# STM32F407_Core.net
KiCad netlist of a schematic drawn in Altium Designer
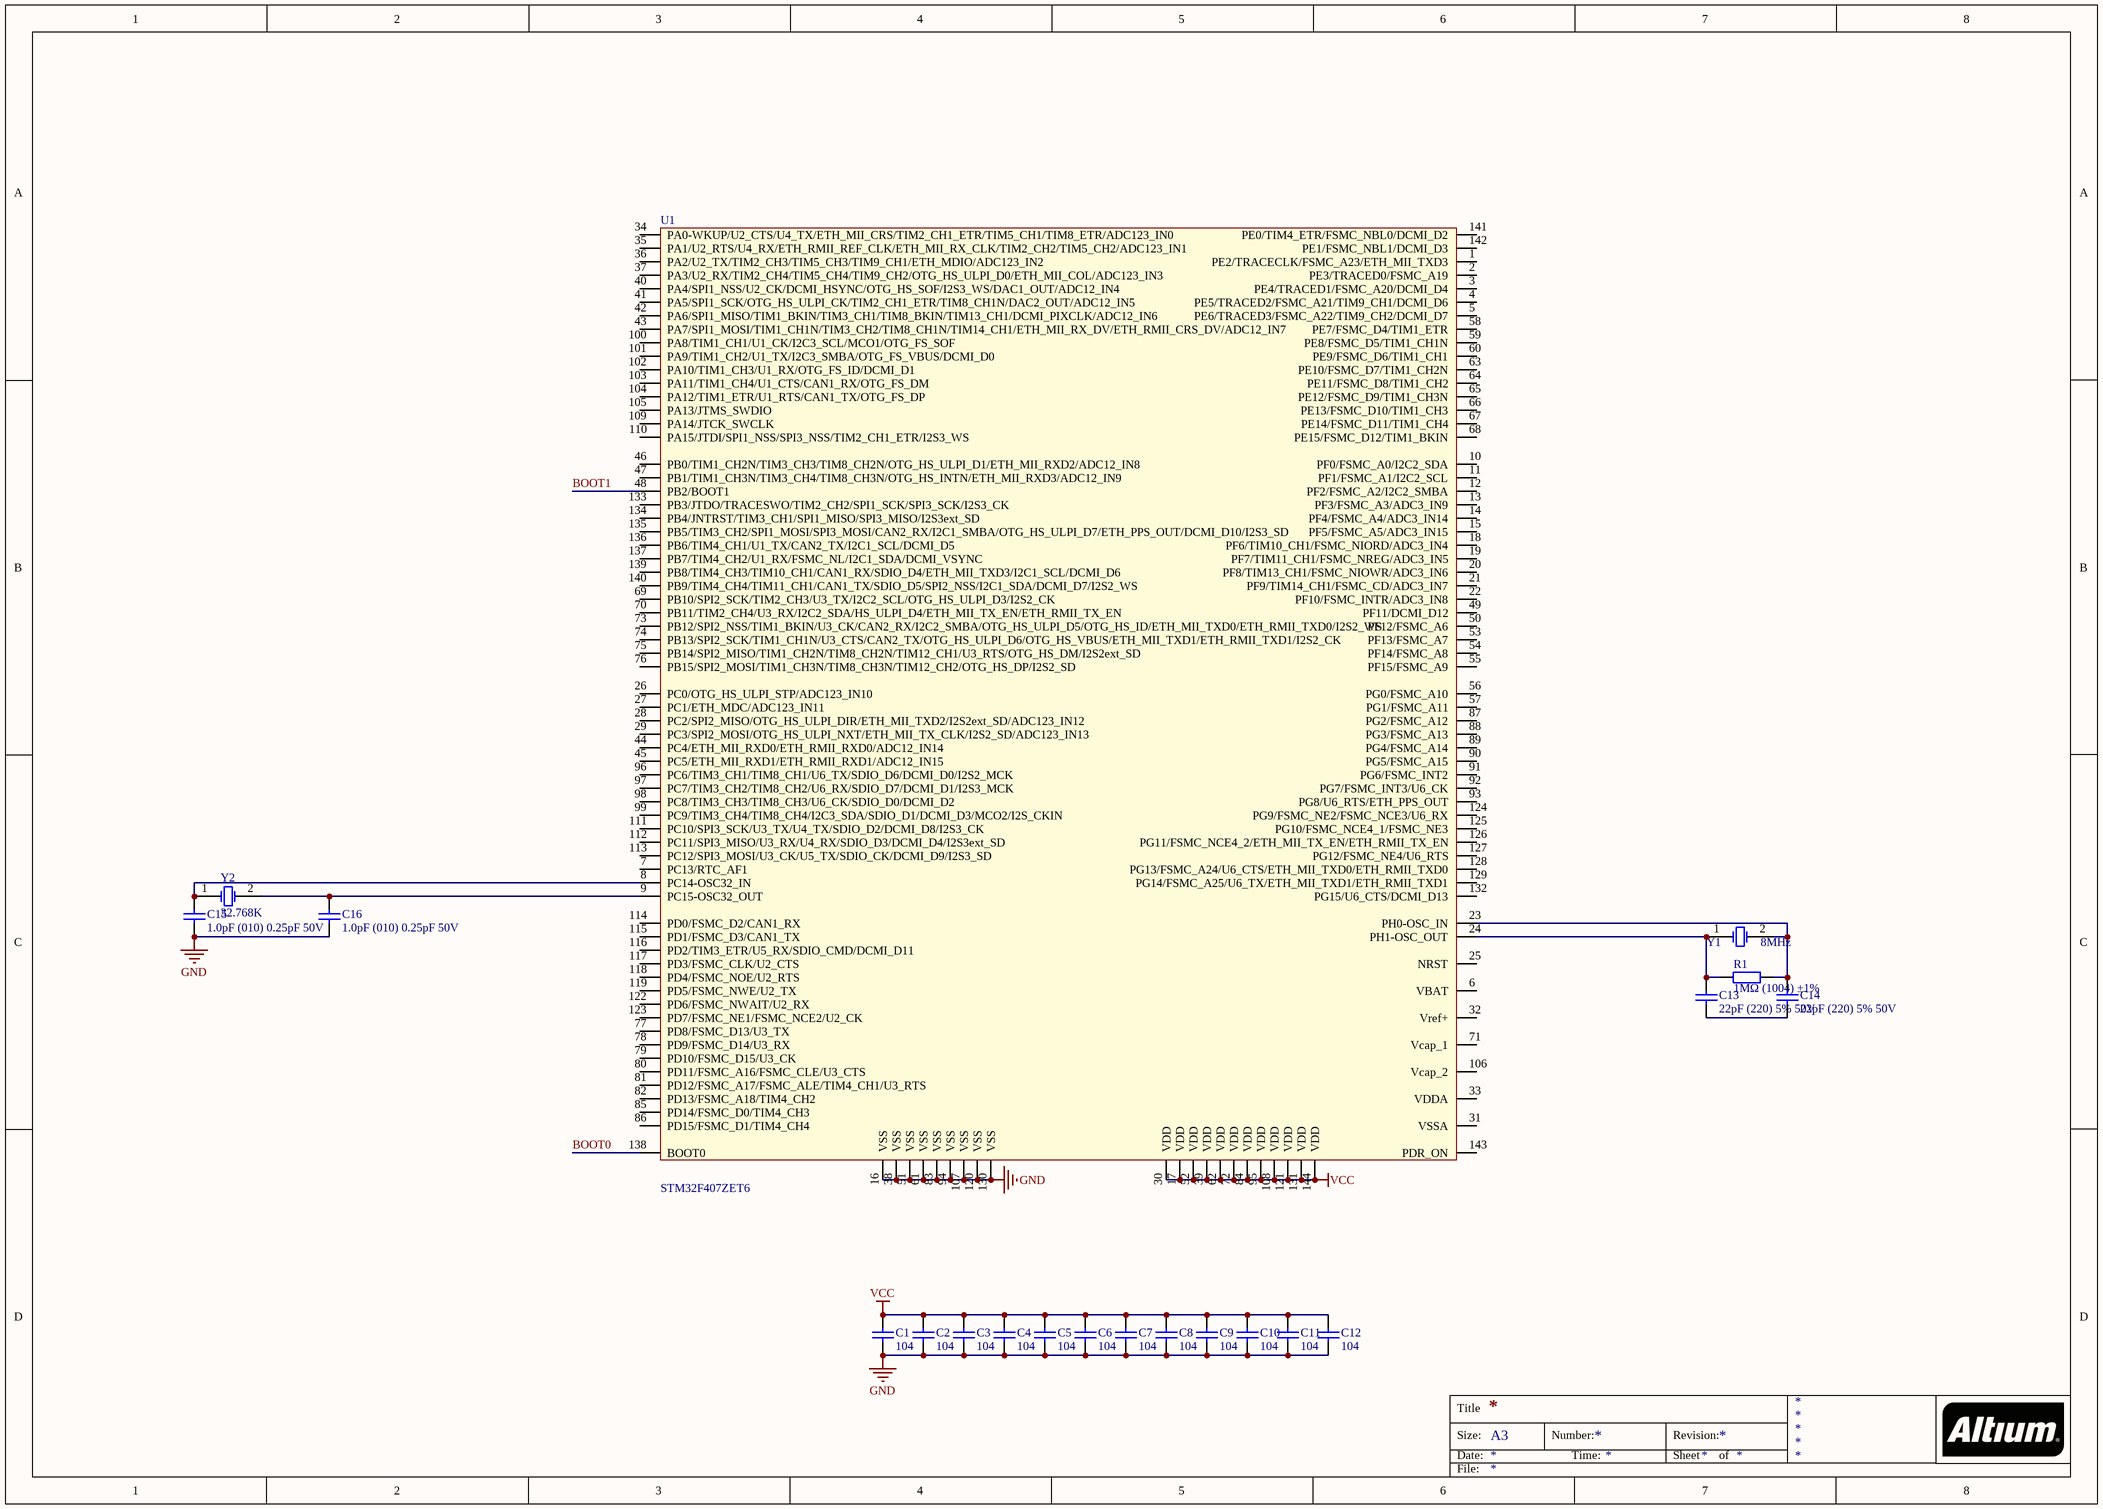
[diagram p0: STM32F407_Core.SchDoc]

(export (version "E")
  (design (tool "Eeschema 10.0.6"))
  (components
    (comp (ref "C1")
      (value "104")
      (footprint "LC-0805_C")
      (description "贴片电容")
      (libsource (lib "Miscellaneous Devices LC") (part "0805 100nF(104) 10% 50V"))
    )
    (comp (ref "C2")
      (value "104")
      (footprint "LC-0805_C")
      (description "贴片电容")
      (libsource (lib "Miscellaneous Devices LC") (part "0805 100nF(104) 10% 50V"))
    )
    (comp (ref "C3")
      (value "104")
      (footprint "LC-0805_C")
      (description "贴片电容")
      (libsource (lib "Miscellaneous Devices LC") (part "0805 100nF(104) 10% 50V"))
    )
    (comp (ref "C4")
      (value "104")
      (footprint "LC-0805_C")
      (description "贴片电容")
      (libsource (lib "Miscellaneous Devices LC") (part "0805 100nF(104) 10% 50V"))
    )
    (comp (ref "C5")
      (value "104")
      (footprint "LC-0805_C")
      (description "贴片电容")
      (libsource (lib "Miscellaneous Devices LC") (part "0805 100nF(104) 10% 50V"))
    )
    (comp (ref "C6")
      (value "104")
      (footprint "LC-0805_C")
      (description "贴片电容")
      (libsource (lib "Miscellaneous Devices LC") (part "0805 100nF(104) 10% 50V"))
    )
    (comp (ref "C7")
      (value "104")
      (footprint "LC-0805_C")
      (description "贴片电容")
      (libsource (lib "Miscellaneous Devices LC") (part "0805 100nF(104) 10% 50V"))
    )
    (comp (ref "C8")
      (value "104")
      (footprint "LC-0805_C")
      (description "贴片电容")
      (libsource (lib "Miscellaneous Devices LC") (part "0805 100nF(104) 10% 50V"))
    )
    (comp (ref "C9")
      (value "104")
      (footprint "LC-0805_C")
      (description "贴片电容")
      (libsource (lib "Miscellaneous Devices LC") (part "0805 100nF(104) 10% 50V"))
    )
    (comp (ref "C10")
      (value "104")
      (footprint "LC-0805_C")
      (description "贴片电容")
      (libsource (lib "Miscellaneous Devices LC") (part "0805 100nF(104) 10% 50V"))
    )
    (comp (ref "C11")
      (value "104")
      (footprint "LC-0805_C")
      (description "贴片电容")
      (libsource (lib "Miscellaneous Devices LC") (part "0805 100nF(104) 10% 50V"))
    )
    (comp (ref "C12")
      (value "104")
      (footprint "LC-0805_C")
      (description "贴片电容")
      (libsource (lib "Miscellaneous Devices LC") (part "0805 100nF(104) 10% 50V"))
    )
    (comp (ref "C13")
      (value "22pF (220) 5% 50V")
      (footprint "LC-0805_C")
      (description "贴片电容")
      (libsource (lib "Miscellaneous Devices LC") (part "0805 22pF (220) 5% 50V"))
    )
    (comp (ref "C14")
      (value "22pF (220) 5% 50V")
      (footprint "LC-0805_C")
      (description "贴片电容")
      (libsource (lib "Miscellaneous Devices LC") (part "0805 22pF (220) 5% 50V"))
    )
    (comp (ref "C15")
      (value "1.0pF (010) 0.25pF 50V")
      (footprint "LC-0805_C")
      (description "贴片电容")
      (libsource (lib "Miscellaneous Devices LC") (part "0805 1.0pF (010) 0.25pF 50V"))
    )
    (comp (ref "C16")
      (value "1.0pF (010) 0.25pF 50V")
      (footprint "LC-0805_C")
      (description "贴片电容")
      (libsource (lib "Miscellaneous Devices LC") (part "0805 1.0pF (010) 0.25pF 50V"))
    )
    (comp (ref "R1")
      (value "1MΩ (1004) ±1%")
      (footprint "LC-0805_R")
      (description "贴片电阻")
      (libsource (lib "Miscellaneous Devices LC") (part "0805 1MΩ (1004) 1%"))
    )
    (comp (ref "U1")
      (value "STM32F407ZET6")
      (footprint "LQFP144")
      (libsource (lib "Explorer STM32F407封装库") (part "STM32F407ZET6"))
    )
    (comp (ref "Y1")
      (value "8MHz")
      (footprint "XTAL_US")
      (description "Crystal Oscillator")
      (fields (field (name "PUBLISHER") "Altium Limited"))
      (libsource (lib "Explorer STM32F407封装库") (part "XTAL"))
    )
    (comp (ref "Y2")
      (value "32.768K")
      (footprint "R38")
      (description "Crystal Oscillator")
      (fields (field (name "PUBLISHER") "Altium Limited"))
      (libsource (lib "Miscellaneous Devices") (part "XTAL"))
    )
  )
  (nets
    (net (code "1") (name "/BOOT0") (class "Default")
      (node (ref "U1") (pin "138") (pinfunction "BOOT0_138") (pintype "passive"))
    )
    (net (code "2") (name "/BOOT1") (class "Default")
      (node (ref "U1") (pin "48") (pinfunction "PB2/BOOT1_48") (pintype "passive"))
    )
    (net (code "3") (name "GND") (class "Default")
      (node (ref "C1") (pin "1") (pinfunction "1_1") (pintype "passive"))
      (node (ref "C10") (pin "1") (pinfunction "1_1") (pintype "passive"))
      (node (ref "C11") (pin "1") (pinfunction "1_1") (pintype "passive"))
      (node (ref "C12") (pin "1") (pinfunction "1_1") (pintype "passive"))
      (node (ref "C15") (pin "1") (pinfunction "1_1") (pintype "passive"))
      (node (ref "C16") (pin "1") (pinfunction "1_1") (pintype "passive"))
      (node (ref "C2") (pin "1") (pinfunction "1_1") (pintype "passive"))
      (node (ref "C3") (pin "1") (pinfunction "1_1") (pintype "passive"))
      (node (ref "C4") (pin "1") (pinfunction "1_1") (pintype "passive"))
      (node (ref "C5") (pin "1") (pinfunction "1_1") (pintype "passive"))
      (node (ref "C6") (pin "1") (pinfunction "1_1") (pintype "passive"))
      (node (ref "C7") (pin "1") (pinfunction "1_1") (pintype "passive"))
      (node (ref "C8") (pin "1") (pinfunction "1_1") (pintype "passive"))
      (node (ref "C9") (pin "1") (pinfunction "1_1") (pintype "passive"))
      (node (ref "U1") (pin "107") (pinfunction "VSS_107") (pintype "passive"))
      (node (ref "U1") (pin "120") (pinfunction "VSS_120") (pintype "passive"))
      (node (ref "U1") (pin "130") (pinfunction "VSS_130") (pintype "passive"))
      (node (ref "U1") (pin "16") (pinfunction "VSS_16") (pintype "passive"))
      (node (ref "U1") (pin "38") (pinfunction "VSS_38") (pintype "passive"))
      (node (ref "U1") (pin "51") (pinfunction "VSS_51") (pintype "passive"))
      (node (ref "U1") (pin "61") (pinfunction "VSS_61") (pintype "passive"))
      (node (ref "U1") (pin "83") (pinfunction "VSS_83") (pintype "passive"))
      (node (ref "U1") (pin "94") (pinfunction "VSS_94") (pintype "passive"))
    )
    (net (code "4") (name "Net-(C13-Pad1)") (class "Default")
      (node (ref "C13") (pin "1") (pinfunction "1_1") (pintype "passive"))
      (node (ref "C14") (pin "1") (pinfunction "1_1") (pintype "passive"))
    )
    (net (code "5") (name "Net-(U1-PC14-OSC32_IN)") (class "Default")
      (node (ref "C15") (pin "2") (pinfunction "2_2") (pintype "passive"))
      (node (ref "U1") (pin "8") (pinfunction "PC14-OSC32_IN_8") (pintype "passive"))
      (node (ref "Y2") (pin "1") (pinfunction "OSC1_1") (pintype "passive"))
    )
    (net (code "6") (name "Net-(U1-PC15-OSC32_OUT)") (class "Default")
      (node (ref "C16") (pin "2") (pinfunction "2_2") (pintype "passive"))
      (node (ref "U1") (pin "9") (pinfunction "PC15-OSC32_OUT_9") (pintype "passive"))
      (node (ref "Y2") (pin "2") (pinfunction "OSC2_2") (pintype "passive"))
    )
    (net (code "7") (name "Net-(U1-PH0-OSC_IN)") (class "Default")
      (node (ref "C14") (pin "2") (pinfunction "2_2") (pintype "passive"))
      (node (ref "R1") (pin "2") (pinfunction "2_2") (pintype "passive"))
      (node (ref "U1") (pin "23") (pinfunction "PH0-OSC_IN_23") (pintype "passive"))
      (node (ref "Y1") (pin "2") (pinfunction "OSC2_2") (pintype "passive"))
    )
    (net (code "8") (name "Net-(U1-PH1-OSC_OUT)") (class "Default")
      (node (ref "C13") (pin "2") (pinfunction "2_2") (pintype "passive"))
      (node (ref "R1") (pin "1") (pinfunction "1_1") (pintype "passive"))
      (node (ref "U1") (pin "24") (pinfunction "PH1-OSC_OUT_24") (pintype "passive"))
      (node (ref "Y1") (pin "1") (pinfunction "OSC1_1") (pintype "passive"))
    )
    (net (code "9") (name "VCC") (class "Default")
      (node (ref "C1") (pin "2") (pinfunction "2_2") (pintype "passive"))
      (node (ref "C10") (pin "2") (pinfunction "2_2") (pintype "passive"))
      (node (ref "C11") (pin "2") (pinfunction "2_2") (pintype "passive"))
      (node (ref "C12") (pin "2") (pinfunction "2_2") (pintype "passive"))
      (node (ref "C2") (pin "2") (pinfunction "2_2") (pintype "passive"))
      (node (ref "C3") (pin "2") (pinfunction "2_2") (pintype "passive"))
      (node (ref "C4") (pin "2") (pinfunction "2_2") (pintype "passive"))
      (node (ref "C5") (pin "2") (pinfunction "2_2") (pintype "passive"))
      (node (ref "C6") (pin "2") (pinfunction "2_2") (pintype "passive"))
      (node (ref "C7") (pin "2") (pinfunction "2_2") (pintype "passive"))
      (node (ref "C8") (pin "2") (pinfunction "2_2") (pintype "passive"))
      (node (ref "C9") (pin "2") (pinfunction "2_2") (pintype "passive"))
      (node (ref "U1") (pin "108") (pinfunction "VDD_108") (pintype "passive"))
      (node (ref "U1") (pin "121") (pinfunction "VDD_121") (pintype "passive"))
      (node (ref "U1") (pin "131") (pinfunction "VDD_131") (pintype "passive"))
      (node (ref "U1") (pin "144") (pinfunction "VDD_144") (pintype "passive"))
      (node (ref "U1") (pin "17") (pinfunction "VDD_17") (pintype "passive"))
      (node (ref "U1") (pin "30") (pinfunction "VDD_30") (pintype "passive"))
      (node (ref "U1") (pin "39") (pinfunction "VDD_39") (pintype "passive"))
      (node (ref "U1") (pin "52") (pinfunction "VDD_52") (pintype "passive"))
      (node (ref "U1") (pin "62") (pinfunction "VDD_62") (pintype "passive"))
      (node (ref "U1") (pin "72") (pinfunction "VDD_72") (pintype "passive"))
      (node (ref "U1") (pin "84") (pinfunction "VDD_84") (pintype "passive"))
      (node (ref "U1") (pin "95") (pinfunction "VDD_95") (pintype "passive"))
    )
    (net (code "10") (name "unconnected-(U1-NRST-Pad25)") (class "Default")
      (node (ref "U1") (pin "25") (pinfunction "NRST_25") (pintype "passive"))
    )
    (net (code "11") (name "unconnected-(U1-PA0-WKUP{slash}U2_CTS{slash}U4_TX{slash}ETH_MII_CRS{slash}TIM2_CH1_ETR{slash}TIM5_CH1{slash}TIM8_ETR{slash}ADC123_IN0-Pad34)") (class "Default")
      (node (ref "U1") (pin "34") (pinfunction "PA0-WKUP/U2_CTS/U4_TX/ETH_MII_CRS/TIM2_CH1_ETR/TIM5_CH1/TIM8_ETR/ADC123_IN0_34") (pintype "passive"))
    )
    (net (code "12") (name "unconnected-(U1-PA1{slash}U2_RTS{slash}U4_RX{slash}ETH_RMII_REF_CLK{slash}ETH_MII_RX_CLK{slash}TIM2_CH2{slash}TIM5_CH2{slash}ADC123_IN1-Pad35)") (class "Default")
      (node (ref "U1") (pin "35") (pinfunction "PA1/U2_RTS/U4_RX/ETH_RMII_REF_CLK/ETH_MII_RX_CLK/TIM2_CH2/TIM5_CH2/ADC123_IN1_35") (pintype "passive"))
    )
    (net (code "13") (name "unconnected-(U1-PA2{slash}U2_TX{slash}TIM2_CH3{slash}TIM5_CH3{slash}TIM9_CH1{slash}ETH_MDIO{slash}ADC123_IN2-Pad36)") (class "Default")
      (node (ref "U1") (pin "36") (pinfunction "PA2/U2_TX/TIM2_CH3/TIM5_CH3/TIM9_CH1/ETH_MDIO/ADC123_IN2_36") (pintype "passive"))
    )
    (net (code "14") (name "unconnected-(U1-PA3{slash}U2_RX{slash}TIM2_CH4{slash}TIM5_CH4{slash}TIM9_CH2{slash}OTG_HS_ULPI_D0{slash}ETH_MII_COL{slash}ADC123_IN3-Pad37)") (class "Default")
      (node (ref "U1") (pin "37") (pinfunction "PA3/U2_RX/TIM2_CH4/TIM5_CH4/TIM9_CH2/OTG_HS_ULPI_D0/ETH_MII_COL/ADC123_IN3_37") (pintype "passive"))
    )
    (net (code "15") (name "unconnected-(U1-PA4{slash}SPI1_NSS{slash}U2_CK{slash}DCMI_HSYNC{slash}OTG_HS_SOF{slash}I2S3_WS{slash}DAC1_OUT{slash}ADC12_IN4-Pad40)") (class "Default")
      (node (ref "U1") (pin "40") (pinfunction "PA4/SPI1_NSS/U2_CK/DCMI_HSYNC/OTG_HS_SOF/I2S3_WS/DAC1_OUT/ADC12_IN4_40") (pintype "passive"))
    )
    (net (code "16") (name "unconnected-(U1-PA5{slash}SPI1_SCK{slash}OTG_HS_ULPI_CK{slash}TIM2_CH1_ETR{slash}TIM8_CH1N{slash}DAC2_OUT{slash}ADC12_IN5-Pad41)") (class "Default")
      (node (ref "U1") (pin "41") (pinfunction "PA5/SPI1_SCK/OTG_HS_ULPI_CK/TIM2_CH1_ETR/TIM8_CH1N/DAC2_OUT/ADC12_IN5_41") (pintype "passive"))
    )
    (net (code "17") (name "unconnected-(U1-PA6{slash}SPI1_MISO{slash}TIM1_BKIN{slash}TIM3_CH1{slash}TIM8_BKIN{slash}TIM13_CH1{slash}DCMI_PIXCLK{slash}ADC12_IN6-Pad42)") (class "Default")
      (node (ref "U1") (pin "42") (pinfunction "PA6/SPI1_MISO/TIM1_BKIN/TIM3_CH1/TIM8_BKIN/TIM13_CH1/DCMI_PIXCLK/ADC12_IN6_42") (pintype "passive"))
    )
    (net (code "18") (name "unconnected-(U1-PA7{slash}SPI1_MOSI{slash}TIM1_CH1N{slash}TIM3_CH2{slash}TIM8_CH1N{slash}TIM14_CH1{slash}ETH_MII_RX_DV{slash}ETH_RMII_CRS_DV{slash}ADC12_IN7-Pad43)") (class "Default")
      (node (ref "U1") (pin "43") (pinfunction "PA7/SPI1_MOSI/TIM1_CH1N/TIM3_CH2/TIM8_CH1N/TIM14_CH1/ETH_MII_RX_DV/ETH_RMII_CRS_DV/ADC12_IN7_43") (pintype "passive"))
    )
    (net (code "19") (name "unconnected-(U1-PA8{slash}TIM1_CH1{slash}U1_CK{slash}I2C3_SCL{slash}MCO1{slash}OTG_FS_SOF-Pad100)") (class "Default")
      (node (ref "U1") (pin "100") (pinfunction "PA8/TIM1_CH1/U1_CK/I2C3_SCL/MCO1/OTG_FS_SOF_100") (pintype "passive"))
    )
    (net (code "20") (name "unconnected-(U1-PA9{slash}TIM1_CH2{slash}U1_TX{slash}I2C3_SMBA{slash}OTG_FS_VBUS{slash}DCMI_D0-Pad101)") (class "Default")
      (node (ref "U1") (pin "101") (pinfunction "PA9/TIM1_CH2/U1_TX/I2C3_SMBA/OTG_FS_VBUS/DCMI_D0_101") (pintype "passive"))
    )
    (net (code "21") (name "unconnected-(U1-PA10{slash}TIM1_CH3{slash}U1_RX{slash}OTG_FS_ID{slash}DCMI_D1-Pad102)") (class "Default")
      (node (ref "U1") (pin "102") (pinfunction "PA10/TIM1_CH3/U1_RX/OTG_FS_ID/DCMI_D1_102") (pintype "passive"))
    )
    (net (code "22") (name "unconnected-(U1-PA11{slash}TIM1_CH4{slash}U1_CTS{slash}CAN1_RX{slash}OTG_FS_DM-Pad103)") (class "Default")
      (node (ref "U1") (pin "103") (pinfunction "PA11/TIM1_CH4/U1_CTS/CAN1_RX/OTG_FS_DM_103") (pintype "passive"))
    )
    (net (code "23") (name "unconnected-(U1-PA12{slash}TIM1_ETR{slash}U1_RTS{slash}CAN1_TX{slash}OTG_FS_DP-Pad104)") (class "Default")
      (node (ref "U1") (pin "104") (pinfunction "PA12/TIM1_ETR/U1_RTS/CAN1_TX/OTG_FS_DP_104") (pintype "passive"))
    )
    (net (code "24") (name "unconnected-(U1-PA13{slash}JTMS_SWDIO-Pad105)") (class "Default")
      (node (ref "U1") (pin "105") (pinfunction "PA13/JTMS_SWDIO_105") (pintype "passive"))
    )
    (net (code "25") (name "unconnected-(U1-PA14{slash}JTCK_SWCLK-Pad109)") (class "Default")
      (node (ref "U1") (pin "109") (pinfunction "PA14/JTCK_SWCLK_109") (pintype "passive"))
    )
    (net (code "26") (name "unconnected-(U1-PA15{slash}JTDI{slash}SPI1_NSS{slash}SPI3_NSS{slash}TIM2_CH1_ETR{slash}I2S3_WS-Pad110)") (class "Default")
      (node (ref "U1") (pin "110") (pinfunction "PA15/JTDI/SPI1_NSS/SPI3_NSS/TIM2_CH1_ETR/I2S3_WS_110") (pintype "passive"))
    )
    (net (code "27") (name "unconnected-(U1-PB0{slash}TIM1_CH2N{slash}TIM3_CH3{slash}TIM8_CH2N{slash}OTG_HS_ULPI_D1{slash}ETH_MII_RXD2{slash}ADC12_IN8-Pad46)") (class "Default")
      (node (ref "U1") (pin "46") (pinfunction "PB0/TIM1_CH2N/TIM3_CH3/TIM8_CH2N/OTG_HS_ULPI_D1/ETH_MII_RXD2/ADC12_IN8_46") (pintype "passive"))
    )
    (net (code "28") (name "unconnected-(U1-PB1{slash}TIM1_CH3N{slash}TIM3_CH4{slash}TIM8_CH3N{slash}OTG_HS_INTN{slash}ETH_MII_RXD3{slash}ADC12_IN9-Pad47)") (class "Default")
      (node (ref "U1") (pin "47") (pinfunction "PB1/TIM1_CH3N/TIM3_CH4/TIM8_CH3N/OTG_HS_INTN/ETH_MII_RXD3/ADC12_IN9_47") (pintype "passive"))
    )
    (net (code "29") (name "unconnected-(U1-PB3{slash}JTDO{slash}TRACESWO{slash}TIM2_CH2{slash}SPI1_SCK{slash}SPI3_SCK{slash}I2S3_CK-Pad133)") (class "Default")
      (node (ref "U1") (pin "133") (pinfunction "PB3/JTDO/TRACESWO/TIM2_CH2/SPI1_SCK/SPI3_SCK/I2S3_CK_133") (pintype "passive"))
    )
    (net (code "30") (name "unconnected-(U1-PB4{slash}JNTRST{slash}TIM3_CH1{slash}SPI1_MISO{slash}SPI3_MISO{slash}I2S3ext_SD-Pad134)") (class "Default")
      (node (ref "U1") (pin "134") (pinfunction "PB4/JNTRST/TIM3_CH1/SPI1_MISO/SPI3_MISO/I2S3ext_SD_134") (pintype "passive"))
    )
    (net (code "31") (name "unconnected-(U1-PB5{slash}TIM3_CH2{slash}SPI1_MOSI{slash}SPI3_MOSI{slash}CAN2_RX{slash}I2C1_SMBA{slash}OTG_HS_ULPI_D7{slash}ETH_PPS_OUT{slash}DCMI_D10{slash}I2S3_SD-Pad135)") (class "Default")
      (node (ref "U1") (pin "135") (pinfunction "PB5/TIM3_CH2/SPI1_MOSI/SPI3_MOSI/CAN2_RX/I2C1_SMBA/OTG_HS_ULPI_D7/ETH_PPS_OUT/DCMI_D10/I2S3_SD_135") (pintype "passive"))
    )
    (net (code "32") (name "unconnected-(U1-PB6{slash}TIM4_CH1{slash}U1_TX{slash}CAN2_TX{slash}I2C1_SCL{slash}DCMI_D5-Pad136)") (class "Default")
      (node (ref "U1") (pin "136") (pinfunction "PB6/TIM4_CH1/U1_TX/CAN2_TX/I2C1_SCL/DCMI_D5_136") (pintype "passive"))
    )
    (net (code "33") (name "unconnected-(U1-PB7{slash}TIM4_CH2{slash}U1_RX{slash}FSMC_NL{slash}I2C1_SDA{slash}DCMI_VSYNC-Pad137)") (class "Default")
      (node (ref "U1") (pin "137") (pinfunction "PB7/TIM4_CH2/U1_RX/FSMC_NL/I2C1_SDA/DCMI_VSYNC_137") (pintype "passive"))
    )
    (net (code "34") (name "unconnected-(U1-PB8{slash}TIM4_CH3{slash}TIM10_CH1{slash}CAN1_RX{slash}SDIO_D4{slash}ETH_MII_TXD3{slash}I2C1_SCL{slash}DCMI_D6-Pad139)") (class "Default")
      (node (ref "U1") (pin "139") (pinfunction "PB8/TIM4_CH3/TIM10_CH1/CAN1_RX/SDIO_D4/ETH_MII_TXD3/I2C1_SCL/DCMI_D6_139") (pintype "passive"))
    )
    (net (code "35") (name "unconnected-(U1-PB9{slash}TIM4_CH4{slash}TIM11_CH1{slash}CAN1_TX{slash}SDIO_D5{slash}SPI2_NSS{slash}I2C1_SDA{slash}DCMI_D7{slash}I2S2_WS-Pad140)") (class "Default")
      (node (ref "U1") (pin "140") (pinfunction "PB9/TIM4_CH4/TIM11_CH1/CAN1_TX/SDIO_D5/SPI2_NSS/I2C1_SDA/DCMI_D7/I2S2_WS_140") (pintype "passive"))
    )
    (net (code "36") (name "unconnected-(U1-PB10{slash}SPI2_SCK{slash}TIM2_CH3{slash}U3_TX{slash}I2C2_SCL{slash}OTG_HS_ULPI_D3{slash}I2S2_CK-Pad69)") (class "Default")
      (node (ref "U1") (pin "69") (pinfunction "PB10/SPI2_SCK/TIM2_CH3/U3_TX/I2C2_SCL/OTG_HS_ULPI_D3/I2S2_CK_69") (pintype "passive"))
    )
    (net (code "37") (name "unconnected-(U1-PB11{slash}TIM2_CH4{slash}U3_RX{slash}I2C2_SDA{slash}HS_ULPI_D4{slash}ETH_MII_TX_EN{slash}ETH_RMII_TX_EN-Pad70)") (class "Default")
      (node (ref "U1") (pin "70") (pinfunction "PB11/TIM2_CH4/U3_RX/I2C2_SDA/HS_ULPI_D4/ETH_MII_TX_EN/ETH_RMII_TX_EN_70") (pintype "passive"))
    )
    (net (code "38") (name "unconnected-(U1-PB12{slash}SPI2_NSS{slash}TIM1_BKIN{slash}U3_CK{slash}CAN2_RX{slash}I2C2_SMBA{slash}OTG_HS_ULPI_D5{slash}OTG_HS_ID{slash}ETH_MII_TXD0{slash}ETH_RMII_TXD0{slash}I2S2_WS-Pad73)") (class "Default")
      (node (ref "U1") (pin "73") (pinfunction "PB12/SPI2_NSS/TIM1_BKIN/U3_CK/CAN2_RX/I2C2_SMBA/OTG_HS_ULPI_D5/OTG_HS_ID/ETH_MII_TXD0/ETH_RMII_TXD0/I2S2_WS_73") (pintype "passive"))
    )
    (net (code "39") (name "unconnected-(U1-PB13{slash}SPI2_SCK{slash}TIM1_CH1N{slash}U3_CTS{slash}CAN2_TX{slash}OTG_HS_ULPI_D6{slash}OTG_HS_VBUS{slash}ETH_MII_TXD1{slash}ETH_RMII_TXD1{slash}I2S2_CK-Pad74)") (class "Default")
      (node (ref "U1") (pin "74") (pinfunction "PB13/SPI2_SCK/TIM1_CH1N/U3_CTS/CAN2_TX/OTG_HS_ULPI_D6/OTG_HS_VBUS/ETH_MII_TXD1/ETH_RMII_TXD1/I2S2_CK_74") (pintype "passive"))
    )
    (net (code "40") (name "unconnected-(U1-PB14{slash}SPI2_MISO{slash}TIM1_CH2N{slash}TIM8_CH2N{slash}TIM12_CH1{slash}U3_RTS{slash}OTG_HS_DM{slash}I2S2ext_SD-Pad75)") (class "Default")
      (node (ref "U1") (pin "75") (pinfunction "PB14/SPI2_MISO/TIM1_CH2N/TIM8_CH2N/TIM12_CH1/U3_RTS/OTG_HS_DM/I2S2ext_SD_75") (pintype "passive"))
    )
    (net (code "41") (name "unconnected-(U1-PB15{slash}SPI2_MOSI{slash}TIM1_CH3N{slash}TIM8_CH3N{slash}TIM12_CH2{slash}OTG_HS_DP{slash}I2S2_SD-Pad76)") (class "Default")
      (node (ref "U1") (pin "76") (pinfunction "PB15/SPI2_MOSI/TIM1_CH3N/TIM8_CH3N/TIM12_CH2/OTG_HS_DP/I2S2_SD_76") (pintype "passive"))
    )
    (net (code "42") (name "unconnected-(U1-PC0{slash}OTG_HS_ULPI_STP{slash}ADC123_IN10-Pad26)") (class "Default")
      (node (ref "U1") (pin "26") (pinfunction "PC0/OTG_HS_ULPI_STP/ADC123_IN10_26") (pintype "passive"))
    )
    (net (code "43") (name "unconnected-(U1-PC1{slash}ETH_MDC{slash}ADC123_IN11-Pad27)") (class "Default")
      (node (ref "U1") (pin "27") (pinfunction "PC1/ETH_MDC/ADC123_IN11_27") (pintype "passive"))
    )
    (net (code "44") (name "unconnected-(U1-PC2{slash}SPI2_MISO{slash}OTG_HS_ULPI_DIR{slash}ETH_MII_TXD2{slash}I2S2ext_SD{slash}ADC123_IN12-Pad28)") (class "Default")
      (node (ref "U1") (pin "28") (pinfunction "PC2/SPI2_MISO/OTG_HS_ULPI_DIR/ETH_MII_TXD2/I2S2ext_SD/ADC123_IN12_28") (pintype "passive"))
    )
    (net (code "45") (name "unconnected-(U1-PC3{slash}SPI2_MOSI{slash}OTG_HS_ULPI_NXT{slash}ETH_MII_TX_CLK{slash}I2S2_SD{slash}ADC123_IN13-Pad29)") (class "Default")
      (node (ref "U1") (pin "29") (pinfunction "PC3/SPI2_MOSI/OTG_HS_ULPI_NXT/ETH_MII_TX_CLK/I2S2_SD/ADC123_IN13_29") (pintype "passive"))
    )
    (net (code "46") (name "unconnected-(U1-PC4{slash}ETH_MII_RXD0{slash}ETH_RMII_RXD0{slash}ADC12_IN14-Pad44)") (class "Default")
      (node (ref "U1") (pin "44") (pinfunction "PC4/ETH_MII_RXD0/ETH_RMII_RXD0/ADC12_IN14_44") (pintype "passive"))
    )
    (net (code "47") (name "unconnected-(U1-PC5{slash}ETH_MII_RXD1{slash}ETH_RMII_RXD1{slash}ADC12_IN15-Pad45)") (class "Default")
      (node (ref "U1") (pin "45") (pinfunction "PC5/ETH_MII_RXD1/ETH_RMII_RXD1/ADC12_IN15_45") (pintype "passive"))
    )
    (net (code "48") (name "unconnected-(U1-PC6{slash}TIM3_CH1{slash}TIM8_CH1{slash}U6_TX{slash}SDIO_D6{slash}DCMI_D0{slash}I2S2_MCK-Pad96)") (class "Default")
      (node (ref "U1") (pin "96") (pinfunction "PC6/TIM3_CH1/TIM8_CH1/U6_TX/SDIO_D6/DCMI_D0/I2S2_MCK_96") (pintype "passive"))
    )
    (net (code "49") (name "unconnected-(U1-PC7{slash}TIM3_CH2{slash}TIM8_CH2{slash}U6_RX{slash}SDIO_D7{slash}DCMI_D1{slash}I2S3_MCK-Pad97)") (class "Default")
      (node (ref "U1") (pin "97") (pinfunction "PC7/TIM3_CH2/TIM8_CH2/U6_RX/SDIO_D7/DCMI_D1/I2S3_MCK_97") (pintype "passive"))
    )
    (net (code "50") (name "unconnected-(U1-PC8{slash}TIM3_CH3{slash}TIM8_CH3{slash}U6_CK{slash}SDIO_D0{slash}DCMI_D2-Pad98)") (class "Default")
      (node (ref "U1") (pin "98") (pinfunction "PC8/TIM3_CH3/TIM8_CH3/U6_CK/SDIO_D0/DCMI_D2_98") (pintype "passive"))
    )
    (net (code "51") (name "unconnected-(U1-PC9{slash}TIM3_CH4{slash}TIM8_CH4{slash}I2C3_SDA{slash}SDIO_D1{slash}DCMI_D3{slash}MCO2{slash}I2S_CKIN-Pad99)") (class "Default")
      (node (ref "U1") (pin "99") (pinfunction "PC9/TIM3_CH4/TIM8_CH4/I2C3_SDA/SDIO_D1/DCMI_D3/MCO2/I2S_CKIN_99") (pintype "passive"))
    )
    (net (code "52") (name "unconnected-(U1-PC10{slash}SPI3_SCK{slash}U3_TX{slash}U4_TX{slash}SDIO_D2{slash}DCMI_D8{slash}I2S3_CK-Pad111)") (class "Default")
      (node (ref "U1") (pin "111") (pinfunction "PC10/SPI3_SCK/U3_TX/U4_TX/SDIO_D2/DCMI_D8/I2S3_CK_111") (pintype "passive"))
    )
    (net (code "53") (name "unconnected-(U1-PC11{slash}SPI3_MISO{slash}U3_RX{slash}U4_RX{slash}SDIO_D3{slash}DCMI_D4{slash}I2S3ext_SD-Pad112)") (class "Default")
      (node (ref "U1") (pin "112") (pinfunction "PC11/SPI3_MISO/U3_RX/U4_RX/SDIO_D3/DCMI_D4/I2S3ext_SD_112") (pintype "passive"))
    )
    (net (code "54") (name "unconnected-(U1-PC12{slash}SPI3_MOSI{slash}U3_CK{slash}U5_TX{slash}SDIO_CK{slash}DCMI_D9{slash}I2S3_SD-Pad113)") (class "Default")
      (node (ref "U1") (pin "113") (pinfunction "PC12/SPI3_MOSI/U3_CK/U5_TX/SDIO_CK/DCMI_D9/I2S3_SD_113") (pintype "passive"))
    )
    (net (code "55") (name "unconnected-(U1-PC13{slash}RTC_AF1-Pad7)") (class "Default")
      (node (ref "U1") (pin "7") (pinfunction "PC13/RTC_AF1_7") (pintype "passive"))
    )
    (net (code "56") (name "unconnected-(U1-PD0{slash}FSMC_D2{slash}CAN1_RX-Pad114)") (class "Default")
      (node (ref "U1") (pin "114") (pinfunction "PD0/FSMC_D2/CAN1_RX_114") (pintype "passive"))
    )
    (net (code "57") (name "unconnected-(U1-PD1{slash}FSMC_D3{slash}CAN1_TX-Pad115)") (class "Default")
      (node (ref "U1") (pin "115") (pinfunction "PD1/FSMC_D3/CAN1_TX_115") (pintype "passive"))
    )
    (net (code "58") (name "unconnected-(U1-PD2{slash}TIM3_ETR{slash}U5_RX{slash}SDIO_CMD{slash}DCMI_D11-Pad116)") (class "Default")
      (node (ref "U1") (pin "116") (pinfunction "PD2/TIM3_ETR/U5_RX/SDIO_CMD/DCMI_D11_116") (pintype "passive"))
    )
    (net (code "59") (name "unconnected-(U1-PD3{slash}FSMC_CLK{slash}U2_CTS-Pad117)") (class "Default")
      (node (ref "U1") (pin "117") (pinfunction "PD3/FSMC_CLK/U2_CTS_117") (pintype "passive"))
    )
    (net (code "60") (name "unconnected-(U1-PD4{slash}FSMC_NOE{slash}U2_RTS-Pad118)") (class "Default")
      (node (ref "U1") (pin "118") (pinfunction "PD4/FSMC_NOE/U2_RTS_118") (pintype "passive"))
    )
    (net (code "61") (name "unconnected-(U1-PD5{slash}FSMC_NWE{slash}U2_TX-Pad119)") (class "Default")
      (node (ref "U1") (pin "119") (pinfunction "PD5/FSMC_NWE/U2_TX_119") (pintype "passive"))
    )
    (net (code "62") (name "unconnected-(U1-PD6{slash}FSMC_NWAIT{slash}U2_RX-Pad122)") (class "Default")
      (node (ref "U1") (pin "122") (pinfunction "PD6/FSMC_NWAIT/U2_RX_122") (pintype "passive"))
    )
    (net (code "63") (name "unconnected-(U1-PD7{slash}FSMC_NE1{slash}FSMC_NCE2{slash}U2_CK-Pad123)") (class "Default")
      (node (ref "U1") (pin "123") (pinfunction "PD7/FSMC_NE1/FSMC_NCE2/U2_CK_123") (pintype "passive"))
    )
    (net (code "64") (name "unconnected-(U1-PD8{slash}FSMC_D13{slash}U3_TX-Pad77)") (class "Default")
      (node (ref "U1") (pin "77") (pinfunction "PD8/FSMC_D13/U3_TX_77") (pintype "passive"))
    )
    (net (code "65") (name "unconnected-(U1-PD9{slash}FSMC_D14{slash}U3_RX-Pad78)") (class "Default")
      (node (ref "U1") (pin "78") (pinfunction "PD9/FSMC_D14/U3_RX_78") (pintype "passive"))
    )
    (net (code "66") (name "unconnected-(U1-PD10{slash}FSMC_D15{slash}U3_CK-Pad79)") (class "Default")
      (node (ref "U1") (pin "79") (pinfunction "PD10/FSMC_D15/U3_CK_79") (pintype "passive"))
    )
    (net (code "67") (name "unconnected-(U1-PD11{slash}FSMC_A16{slash}FSMC_CLE{slash}U3_CTS-Pad80)") (class "Default")
      (node (ref "U1") (pin "80") (pinfunction "PD11/FSMC_A16/FSMC_CLE/U3_CTS_80") (pintype "passive"))
    )
    (net (code "68") (name "unconnected-(U1-PD12{slash}FSMC_A17{slash}FSMC_ALE{slash}TIM4_CH1{slash}U3_RTS-Pad81)") (class "Default")
      (node (ref "U1") (pin "81") (pinfunction "PD12/FSMC_A17/FSMC_ALE/TIM4_CH1/U3_RTS_81") (pintype "passive"))
    )
    (net (code "69") (name "unconnected-(U1-PD13{slash}FSMC_A18{slash}TIM4_CH2-Pad82)") (class "Default")
      (node (ref "U1") (pin "82") (pinfunction "PD13/FSMC_A18/TIM4_CH2_82") (pintype "passive"))
    )
    (net (code "70") (name "unconnected-(U1-PD14{slash}FSMC_D0{slash}TIM4_CH3-Pad85)") (class "Default")
      (node (ref "U1") (pin "85") (pinfunction "PD14/FSMC_D0/TIM4_CH3_85") (pintype "passive"))
    )
    (net (code "71") (name "unconnected-(U1-PD15{slash}FSMC_D1{slash}TIM4_CH4-Pad86)") (class "Default")
      (node (ref "U1") (pin "86") (pinfunction "PD15/FSMC_D1/TIM4_CH4_86") (pintype "passive"))
    )
    (net (code "72") (name "unconnected-(U1-PDR_ON-Pad143)") (class "Default")
      (node (ref "U1") (pin "143") (pinfunction "PDR_ON_143") (pintype "passive"))
    )
    (net (code "73") (name "unconnected-(U1-PE0{slash}TIM4_ETR{slash}FSMC_NBL0{slash}DCMI_D2-Pad141)") (class "Default")
      (node (ref "U1") (pin "141") (pinfunction "PE0/TIM4_ETR/FSMC_NBL0/DCMI_D2_141") (pintype "passive"))
    )
    (net (code "74") (name "unconnected-(U1-PE1{slash}FSMC_NBL1{slash}DCMI_D3-Pad142)") (class "Default")
      (node (ref "U1") (pin "142") (pinfunction "PE1/FSMC_NBL1/DCMI_D3_142") (pintype "passive"))
    )
    (net (code "75") (name "unconnected-(U1-PE2{slash}TRACECLK{slash}FSMC_A23{slash}ETH_MII_TXD3-Pad1)") (class "Default")
      (node (ref "U1") (pin "1") (pinfunction "PE2/TRACECLK/FSMC_A23/ETH_MII_TXD3_1") (pintype "passive"))
    )
    (net (code "76") (name "unconnected-(U1-PE3{slash}TRACED0{slash}FSMC_A19-Pad2)") (class "Default")
      (node (ref "U1") (pin "2") (pinfunction "PE3/TRACED0/FSMC_A19_2") (pintype "passive"))
    )
    (net (code "77") (name "unconnected-(U1-PE4{slash}TRACED1{slash}FSMC_A20{slash}DCMI_D4-Pad3)") (class "Default")
      (node (ref "U1") (pin "3") (pinfunction "PE4/TRACED1/FSMC_A20/DCMI_D4_3") (pintype "passive"))
    )
    (net (code "78") (name "unconnected-(U1-PE5{slash}TRACED2{slash}FSMC_A21{slash}TIM9_CH1{slash}DCMI_D6-Pad4)") (class "Default")
      (node (ref "U1") (pin "4") (pinfunction "PE5/TRACED2/FSMC_A21/TIM9_CH1/DCMI_D6_4") (pintype "passive"))
    )
    (net (code "79") (name "unconnected-(U1-PE6{slash}TRACED3{slash}FSMC_A22{slash}TIM9_CH2{slash}DCMI_D7-Pad5)") (class "Default")
      (node (ref "U1") (pin "5") (pinfunction "PE6/TRACED3/FSMC_A22/TIM9_CH2/DCMI_D7_5") (pintype "passive"))
    )
    (net (code "80") (name "unconnected-(U1-PE7{slash}FSMC_D4{slash}TIM1_ETR-Pad58)") (class "Default")
      (node (ref "U1") (pin "58") (pinfunction "PE7/FSMC_D4/TIM1_ETR_58") (pintype "passive"))
    )
    (net (code "81") (name "unconnected-(U1-PE8{slash}FSMC_D5{slash}TIM1_CH1N-Pad59)") (class "Default")
      (node (ref "U1") (pin "59") (pinfunction "PE8/FSMC_D5/TIM1_CH1N_59") (pintype "passive"))
    )
    (net (code "82") (name "unconnected-(U1-PE9{slash}FSMC_D6{slash}TIM1_CH1-Pad60)") (class "Default")
      (node (ref "U1") (pin "60") (pinfunction "PE9/FSMC_D6/TIM1_CH1_60") (pintype "passive"))
    )
    (net (code "83") (name "unconnected-(U1-PE10{slash}FSMC_D7{slash}TIM1_CH2N-Pad63)") (class "Default")
      (node (ref "U1") (pin "63") (pinfunction "PE10/FSMC_D7/TIM1_CH2N_63") (pintype "passive"))
    )
    (net (code "84") (name "unconnected-(U1-PE11{slash}FSMC_D8{slash}TIM1_CH2-Pad64)") (class "Default")
      (node (ref "U1") (pin "64") (pinfunction "PE11/FSMC_D8/TIM1_CH2_64") (pintype "passive"))
    )
    (net (code "85") (name "unconnected-(U1-PE12{slash}FSMC_D9{slash}TIM1_CH3N-Pad65)") (class "Default")
      (node (ref "U1") (pin "65") (pinfunction "PE12/FSMC_D9/TIM1_CH3N_65") (pintype "passive"))
    )
    (net (code "86") (name "unconnected-(U1-PE13{slash}FSMC_D10{slash}TIM1_CH3-Pad66)") (class "Default")
      (node (ref "U1") (pin "66") (pinfunction "PE13/FSMC_D10/TIM1_CH3_66") (pintype "passive"))
    )
    (net (code "87") (name "unconnected-(U1-PE14{slash}FSMC_D11{slash}TIM1_CH4-Pad67)") (class "Default")
      (node (ref "U1") (pin "67") (pinfunction "PE14/FSMC_D11/TIM1_CH4_67") (pintype "passive"))
    )
    (net (code "88") (name "unconnected-(U1-PE15{slash}FSMC_D12{slash}TIM1_BKIN-Pad68)") (class "Default")
      (node (ref "U1") (pin "68") (pinfunction "PE15/FSMC_D12/TIM1_BKIN_68") (pintype "passive"))
    )
    (net (code "89") (name "unconnected-(U1-PF0{slash}FSMC_A0{slash}I2C2_SDA-Pad10)") (class "Default")
      (node (ref "U1") (pin "10") (pinfunction "PF0/FSMC_A0/I2C2_SDA_10") (pintype "passive"))
    )
    (net (code "90") (name "unconnected-(U1-PF1{slash}FSMC_A1{slash}I2C2_SCL-Pad11)") (class "Default")
      (node (ref "U1") (pin "11") (pinfunction "PF1/FSMC_A1/I2C2_SCL_11") (pintype "passive"))
    )
    (net (code "91") (name "unconnected-(U1-PF2{slash}FSMC_A2{slash}I2C2_SMBA-Pad12)") (class "Default")
      (node (ref "U1") (pin "12") (pinfunction "PF2/FSMC_A2/I2C2_SMBA_12") (pintype "passive"))
    )
    (net (code "92") (name "unconnected-(U1-PF3{slash}FSMC_A3{slash}ADC3_IN9-Pad13)") (class "Default")
      (node (ref "U1") (pin "13") (pinfunction "PF3/FSMC_A3/ADC3_IN9_13") (pintype "passive"))
    )
    (net (code "93") (name "unconnected-(U1-PF4{slash}FSMC_A4{slash}ADC3_IN14-Pad14)") (class "Default")
      (node (ref "U1") (pin "14") (pinfunction "PF4/FSMC_A4/ADC3_IN14_14") (pintype "passive"))
    )
    (net (code "94") (name "unconnected-(U1-PF5{slash}FSMC_A5{slash}ADC3_IN15-Pad15)") (class "Default")
      (node (ref "U1") (pin "15") (pinfunction "PF5/FSMC_A5/ADC3_IN15_15") (pintype "passive"))
    )
    (net (code "95") (name "unconnected-(U1-PF6{slash}TIM10_CH1{slash}FSMC_NIORD{slash}ADC3_IN4-Pad18)") (class "Default")
      (node (ref "U1") (pin "18") (pinfunction "PF6/TIM10_CH1/FSMC_NIORD/ADC3_IN4_18") (pintype "passive"))
    )
    (net (code "96") (name "unconnected-(U1-PF7{slash}TIM11_CH1{slash}FSMC_NREG{slash}ADC3_IN5-Pad19)") (class "Default")
      (node (ref "U1") (pin "19") (pinfunction "PF7/TIM11_CH1/FSMC_NREG/ADC3_IN5_19") (pintype "passive"))
    )
    (net (code "97") (name "unconnected-(U1-PF8{slash}TIM13_CH1{slash}FSMC_NIOWR{slash}ADC3_IN6-Pad20)") (class "Default")
      (node (ref "U1") (pin "20") (pinfunction "PF8/TIM13_CH1/FSMC_NIOWR/ADC3_IN6_20") (pintype "passive"))
    )
    (net (code "98") (name "unconnected-(U1-PF9{slash}TIM14_CH1{slash}FSMC_CD{slash}ADC3_IN7-Pad21)") (class "Default")
      (node (ref "U1") (pin "21") (pinfunction "PF9/TIM14_CH1/FSMC_CD/ADC3_IN7_21") (pintype "passive"))
    )
    (net (code "99") (name "unconnected-(U1-PF10{slash}FSMC_INTR{slash}ADC3_IN8-Pad22)") (class "Default")
      (node (ref "U1") (pin "22") (pinfunction "PF10/FSMC_INTR/ADC3_IN8_22") (pintype "passive"))
    )
    (net (code "100") (name "unconnected-(U1-PF11{slash}DCMI_D12-Pad49)") (class "Default")
      (node (ref "U1") (pin "49") (pinfunction "PF11/DCMI_D12_49") (pintype "passive"))
    )
    (net (code "101") (name "unconnected-(U1-PF12{slash}FSMC_A6-Pad50)") (class "Default")
      (node (ref "U1") (pin "50") (pinfunction "PF12/FSMC_A6_50") (pintype "passive"))
    )
    (net (code "102") (name "unconnected-(U1-PF13{slash}FSMC_A7-Pad53)") (class "Default")
      (node (ref "U1") (pin "53") (pinfunction "PF13/FSMC_A7_53") (pintype "passive"))
    )
    (net (code "103") (name "unconnected-(U1-PF14{slash}FSMC_A8-Pad54)") (class "Default")
      (node (ref "U1") (pin "54") (pinfunction "PF14/FSMC_A8_54") (pintype "passive"))
    )
    (net (code "104") (name "unconnected-(U1-PF15{slash}FSMC_A9-Pad55)") (class "Default")
      (node (ref "U1") (pin "55") (pinfunction "PF15/FSMC_A9_55") (pintype "passive"))
    )
    (net (code "105") (name "unconnected-(U1-PG0{slash}FSMC_A10-Pad56)") (class "Default")
      (node (ref "U1") (pin "56") (pinfunction "PG0/FSMC_A10_56") (pintype "passive"))
    )
    (net (code "106") (name "unconnected-(U1-PG1{slash}FSMC_A11-Pad57)") (class "Default")
      (node (ref "U1") (pin "57") (pinfunction "PG1/FSMC_A11_57") (pintype "passive"))
    )
    (net (code "107") (name "unconnected-(U1-PG2{slash}FSMC_A12-Pad87)") (class "Default")
      (node (ref "U1") (pin "87") (pinfunction "PG2/FSMC_A12_87") (pintype "passive"))
    )
    (net (code "108") (name "unconnected-(U1-PG3{slash}FSMC_A13-Pad88)") (class "Default")
      (node (ref "U1") (pin "88") (pinfunction "PG3/FSMC_A13_88") (pintype "passive"))
    )
    (net (code "109") (name "unconnected-(U1-PG4{slash}FSMC_A14-Pad89)") (class "Default")
      (node (ref "U1") (pin "89") (pinfunction "PG4/FSMC_A14_89") (pintype "passive"))
    )
    (net (code "110") (name "unconnected-(U1-PG5{slash}FSMC_A15-Pad90)") (class "Default")
      (node (ref "U1") (pin "90") (pinfunction "PG5/FSMC_A15_90") (pintype "passive"))
    )
    (net (code "111") (name "unconnected-(U1-PG6{slash}FSMC_INT2-Pad91)") (class "Default")
      (node (ref "U1") (pin "91") (pinfunction "PG6/FSMC_INT2_91") (pintype "passive"))
    )
    (net (code "112") (name "unconnected-(U1-PG7{slash}FSMC_INT3{slash}U6_CK-Pad92)") (class "Default")
      (node (ref "U1") (pin "92") (pinfunction "PG7/FSMC_INT3/U6_CK_92") (pintype "passive"))
    )
    (net (code "113") (name "unconnected-(U1-PG8{slash}U6_RTS{slash}ETH_PPS_OUT-Pad93)") (class "Default")
      (node (ref "U1") (pin "93") (pinfunction "PG8/U6_RTS/ETH_PPS_OUT_93") (pintype "passive"))
    )
    (net (code "114") (name "unconnected-(U1-PG9{slash}FSMC_NE2{slash}FSMC_NCE3{slash}U6_RX-Pad124)") (class "Default")
      (node (ref "U1") (pin "124") (pinfunction "PG9/FSMC_NE2/FSMC_NCE3/U6_RX_124") (pintype "passive"))
    )
    (net (code "115") (name "unconnected-(U1-PG10{slash}FSMC_NCE4_1{slash}FSMC_NE3-Pad125)") (class "Default")
      (node (ref "U1") (pin "125") (pinfunction "PG10/FSMC_NCE4_1/FSMC_NE3_125") (pintype "passive"))
    )
    (net (code "116") (name "unconnected-(U1-PG11{slash}FSMC_NCE4_2{slash}ETH_MII_TX_EN{slash}ETH_RMII_TX_EN-Pad126)") (class "Default")
      (node (ref "U1") (pin "126") (pinfunction "PG11/FSMC_NCE4_2/ETH_MII_TX_EN/ETH_RMII_TX_EN_126") (pintype "passive"))
    )
    (net (code "117") (name "unconnected-(U1-PG12{slash}FSMC_NE4{slash}U6_RTS-Pad127)") (class "Default")
      (node (ref "U1") (pin "127") (pinfunction "PG12/FSMC_NE4/U6_RTS_127") (pintype "passive"))
    )
    (net (code "118") (name "unconnected-(U1-PG13{slash}FSMC_A24{slash}U6_CTS{slash}ETH_MII_TXD0{slash}ETH_RMII_TXD0-Pad128)") (class "Default")
      (node (ref "U1") (pin "128") (pinfunction "PG13/FSMC_A24/U6_CTS/ETH_MII_TXD0/ETH_RMII_TXD0_128") (pintype "passive"))
    )
    (net (code "119") (name "unconnected-(U1-PG14{slash}FSMC_A25{slash}U6_TX{slash}ETH_MII_TXD1{slash}ETH_RMII_TXD1-Pad129)") (class "Default")
      (node (ref "U1") (pin "129") (pinfunction "PG14/FSMC_A25/U6_TX/ETH_MII_TXD1/ETH_RMII_TXD1_129") (pintype "passive"))
    )
    (net (code "120") (name "unconnected-(U1-PG15{slash}U6_CTS{slash}DCMI_D13-Pad132)") (class "Default")
      (node (ref "U1") (pin "132") (pinfunction "PG15/U6_CTS/DCMI_D13_132") (pintype "passive"))
    )
    (net (code "121") (name "unconnected-(U1-VBAT-Pad6)") (class "Default")
      (node (ref "U1") (pin "6") (pinfunction "VBAT_6") (pintype "passive"))
    )
    (net (code "122") (name "unconnected-(U1-VDDA-Pad33)") (class "Default")
      (node (ref "U1") (pin "33") (pinfunction "VDDA_33") (pintype "passive"))
    )
    (net (code "123") (name "unconnected-(U1-VSSA-Pad31)") (class "Default")
      (node (ref "U1") (pin "31") (pinfunction "VSSA_31") (pintype "passive"))
    )
    (net (code "124") (name "unconnected-(U1-Vcap_1-Pad71)") (class "Default")
      (node (ref "U1") (pin "71") (pinfunction "Vcap_1_71") (pintype "passive"))
    )
    (net (code "125") (name "unconnected-(U1-Vcap_2-Pad106)") (class "Default")
      (node (ref "U1") (pin "106") (pinfunction "Vcap_2_106") (pintype "passive"))
    )
    (net (code "126") (name "unconnected-(U1-Vref+-Pad32)") (class "Default")
      (node (ref "U1") (pin "32") (pinfunction "Vref+_32") (pintype "passive"))
    )
  )
)
